# GSM.net
KiCad netlist of a schematic drawn in Altium Designer
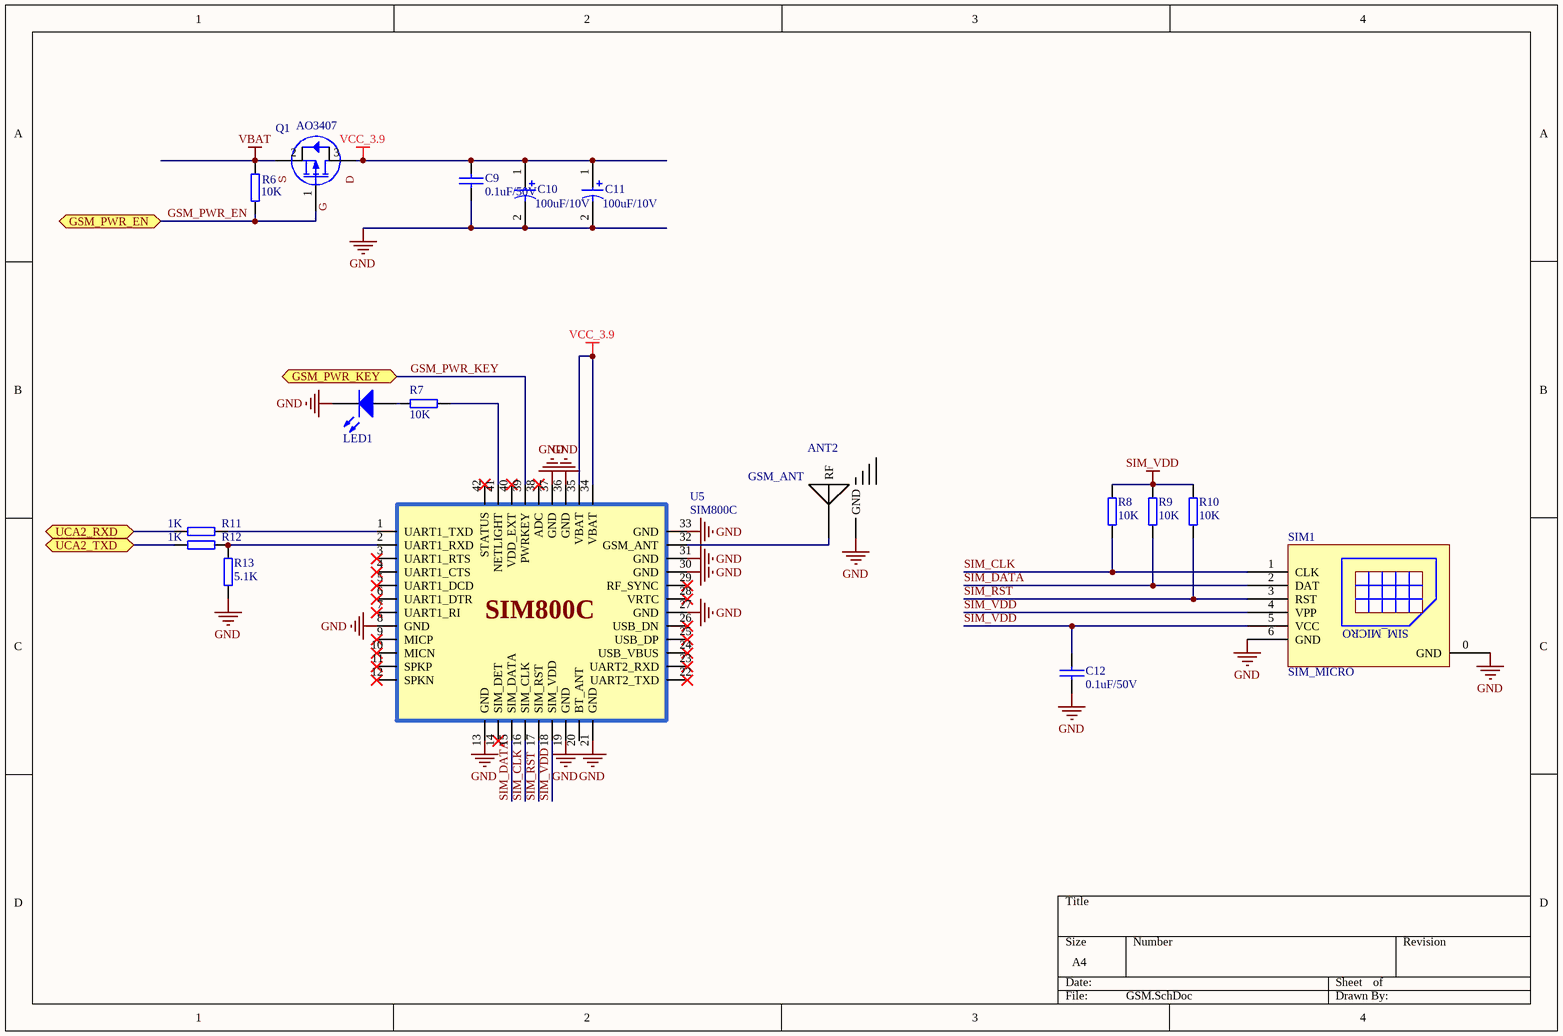
[diagram p0: GSM.SchDoc]

(export (version "E")
  (design (tool "Eeschema 10.0.6"))
  (components
    (comp (ref "ANT2")
      (value "GSM_ANT")
      (footprint "IPEX")
      (description "passive_antenna")
      (libsource (lib "GBOX_V2") (part "GSM_ANT_1"))
    )
    (comp (ref "C9")
      (value "0.1uF/50V")
      (footprint "0603C")
      (description "Capacitor")
      (libsource (lib "0603C") (part "CAP"))
    )
    (comp (ref "C10") (value "100uF/10V") (footprint "CAPTANC") (libsource (lib "*") (part "CAP2")))
    (comp (ref "C11") (value "100uF/10V") (footprint "CAPTANC") (libsource (lib "*") (part "CAP2")))
    (comp (ref "C12") (value "0.1uF/50V") (footprint "0603C") (libsource (lib "Schlib") (part "0603C")))
    (comp (ref "LED1")
      (value "YLED")
      (footprint "LED-0603")
      (description "BLUE LED")
      (fields (field (name "PUBLISHER") "Altium Limited"))
      (libsource (lib "Schlib") (part "LED3"))
    )
    (comp (ref "Q1")
      (value "AO3407")
      (footprint "SOT23")
      (description "P-Channel MOSFET")
      (fields (field (name "PUBLISHER") "Altium Limited"))
      (libsource (lib "SCT1212V100") (part "AO3401"))
    )
    (comp (ref "R6") (value "10K") (footprint "0603R") (libsource (lib "dtu02") (part "RES2A")))
    (comp (ref "R7") (value "10K") (footprint "0603R") (libsource (lib "dtu02") (part "RES2A")))
    (comp (ref "R8") (value "10K") (footprint "0603R") (libsource (lib "dtu02") (part "RES2A")))
    (comp (ref "R9") (value "10K") (footprint "0603R") (libsource (lib "dtu02") (part "RES2A")))
    (comp (ref "R10") (value "10K") (footprint "0603R") (libsource (lib "dtu02") (part "RES2A")))
    (comp (ref "R11") (value "1K") (footprint "0603R") (libsource (lib "dtu02") (part "RES2A")))
    (comp (ref "R12") (value "1K") (footprint "0603R") (libsource (lib "dtu02") (part "RES2A")))
    (comp (ref "R13") (value "5.1K") (footprint "0603R") (libsource (lib "dtu02") (part "RES2A")))
    (comp (ref "SIM1")
      (value "SIM_MICRO")
      (footprint "SIM_MICRO")
      (libsource (lib "GBOX_V2") (part "SIM_MICRO"))
    )
    (comp (ref "U5") (value "SIM800C") (footprint "SIM800C") (libsource (lib "GBOX_V2") (part "SIM800C")))
  )
  (nets
    (net (code "1") (name "/GSM_PWR_EN") (class "Default")
      (node (ref "Q1") (pin "1") (pinfunction "G_1") (pintype "passive"))
      (node (ref "R6") (pin "2") (pintype "passive"))
    )
    (net (code "2") (name "/GSM_PWR_KEY") (class "Default")
      (node (ref "U5") (pin "39") (pinfunction "PWRKEY_39") (pintype "passive"))
    )
    (net (code "3") (name "/SIM_CLK") (class "Default")
      (node (ref "R8") (pin "2") (pintype "passive"))
      (node (ref "SIM1") (pin "1") (pinfunction "CLK_1") (pintype "passive"))
      (node (ref "U5") (pin "16") (pinfunction "SIM_CLK_16") (pintype "passive"))
    )
    (net (code "4") (name "/SIM_DATA") (class "Default")
      (node (ref "R9") (pin "2") (pintype "passive"))
      (node (ref "SIM1") (pin "2") (pinfunction "DAT_2") (pintype "passive"))
      (node (ref "U5") (pin "15") (pinfunction "SIM_DATA_15") (pintype "passive"))
    )
    (net (code "5") (name "/SIM_RST") (class "Default")
      (node (ref "R10") (pin "2") (pintype "passive"))
      (node (ref "SIM1") (pin "3") (pinfunction "RST_3") (pintype "passive"))
      (node (ref "U5") (pin "17") (pinfunction "SIM_RST_17") (pintype "passive"))
    )
    (net (code "6") (name "/UCA2_RXD") (class "Default") (node (ref "R11") (pin "1") (pintype "passive")))
    (net (code "7") (name "/UCA2_TXD") (class "Default") (node (ref "R12") (pin "1") (pintype "passive")))
    (net (code "8") (name "GND") (class "Default")
      (node (ref "ANT2") (pin "1") (pinfunction "GND_1") (pintype "passive"))
      (node (ref "C10") (pin "2") (pinfunction "2_2") (pintype "passive"))
      (node (ref "C11") (pin "2") (pinfunction "2_2") (pintype "passive"))
      (node (ref "C12") (pin "2") (pintype "passive"))
      (node (ref "C9") (pin "2") (pinfunction "2_2") (pintype "passive"))
      (node (ref "LED1") (pin "2") (pinfunction "K_2") (pintype "passive"))
      (node (ref "R13") (pin "2") (pintype "passive"))
      (node (ref "SIM1") (pin "0") (pinfunction "GND_0") (pintype "passive"))
      (node (ref "SIM1") (pin "6") (pinfunction "GND_6") (pintype "passive"))
      (node (ref "U5") (pin "13") (pinfunction "GND_13") (pintype "passive"))
      (node (ref "U5") (pin "19") (pinfunction "GND_19") (pintype "passive"))
      (node (ref "U5") (pin "21") (pinfunction "GND_21") (pintype "passive"))
      (node (ref "U5") (pin "27") (pinfunction "GND_27") (pintype "passive"))
      (node (ref "U5") (pin "30") (pinfunction "GND_30") (pintype "passive"))
      (node (ref "U5") (pin "31") (pinfunction "GND_31") (pintype "passive"))
      (node (ref "U5") (pin "33") (pinfunction "GND_33") (pintype "passive"))
      (node (ref "U5") (pin "36") (pinfunction "GND_36") (pintype "passive"))
      (node (ref "U5") (pin "37") (pinfunction "GND_37") (pintype "passive"))
      (node (ref "U5") (pin "8") (pinfunction "GND_8") (pintype "passive"))
    )
    (net (code "9") (name "Net-(ANT2-RF)") (class "Default")
      (node (ref "ANT2") (pin "2") (pinfunction "RF_2") (pintype "passive"))
      (node (ref "U5") (pin "32") (pinfunction "GSM_ANT_32") (pintype "passive"))
    )
    (net (code "10") (name "Net-(LED1-A)") (class "Default")
      (node (ref "LED1") (pin "1") (pinfunction "A_1") (pintype "passive"))
      (node (ref "R7") (pin "2") (pintype "passive"))
    )
    (net (code "11") (name "Net-(U5-NETLIGHT)") (class "Default")
      (node (ref "R7") (pin "1") (pintype "passive"))
      (node (ref "U5") (pin "41") (pinfunction "NETLIGHT_41") (pintype "passive"))
    )
    (net (code "12") (name "Net-(U5-UART1_RXD)") (class "Default")
      (node (ref "R12") (pin "2") (pintype "passive"))
      (node (ref "R13") (pin "1") (pintype "passive"))
      (node (ref "U5") (pin "2") (pinfunction "UART1_RXD_2") (pintype "passive"))
    )
    (net (code "13") (name "Net-(U5-UART1_TXD)") (class "Default")
      (node (ref "R11") (pin "2") (pintype "passive"))
      (node (ref "U5") (pin "1") (pinfunction "UART1_TXD_1") (pintype "passive"))
    )
    (net (code "14") (name "SIM_VDD") (class "Default")
      (node (ref "C12") (pin "1") (pintype "passive"))
      (node (ref "R10") (pin "1") (pintype "passive"))
      (node (ref "R8") (pin "1") (pintype "passive"))
      (node (ref "R9") (pin "1") (pintype "passive"))
      (node (ref "SIM1") (pin "4") (pinfunction "VPP_4") (pintype "passive"))
      (node (ref "SIM1") (pin "5") (pinfunction "VCC_5") (pintype "passive"))
      (node (ref "U5") (pin "18") (pinfunction "SIM_VDD_18") (pintype "passive"))
    )
    (net (code "15") (name "VBAT") (class "Default")
      (node (ref "Q1") (pin "2") (pinfunction "S_2") (pintype "passive"))
      (node (ref "R6") (pin "1") (pintype "passive"))
    )
    (net (code "16") (name "VCC_3.9") (class "Default")
      (node (ref "C10") (pin "1") (pinfunction "1_1") (pintype "passive"))
      (node (ref "C11") (pin "1") (pinfunction "1_1") (pintype "passive"))
      (node (ref "C9") (pin "1") (pinfunction "1_1") (pintype "passive"))
      (node (ref "Q1") (pin "3") (pinfunction "D_3") (pintype "passive"))
      (node (ref "U5") (pin "34") (pinfunction "VBAT_34") (pintype "passive"))
      (node (ref "U5") (pin "35") (pinfunction "VBAT_35") (pintype "passive"))
    )
    (net (code "17") (name "unconnected-(U5-ADC-Pad38)") (class "Default")
      (node (ref "U5") (pin "38") (pinfunction "ADC_38") (pintype "passive+no_connect"))
    )
    (net (code "18") (name "unconnected-(U5-BT_ANT-Pad20)") (class "Default")
      (node (ref "U5") (pin "20") (pinfunction "BT_ANT_20") (pintype "passive"))
    )
    (net (code "19") (name "unconnected-(U5-MICN-Pad10)") (class "Default")
      (node (ref "U5") (pin "10") (pinfunction "MICN_10") (pintype "passive+no_connect"))
    )
    (net (code "20") (name "unconnected-(U5-MICP-Pad9)") (class "Default")
      (node (ref "U5") (pin "9") (pinfunction "MICP_9") (pintype "passive+no_connect"))
    )
    (net (code "21") (name "unconnected-(U5-RF_SYNC-Pad29)") (class "Default")
      (node (ref "U5") (pin "29") (pinfunction "RF_SYNC_29") (pintype "passive+no_connect"))
    )
    (net (code "22") (name "unconnected-(U5-SIM_DET-Pad14)") (class "Default")
      (node (ref "U5") (pin "14") (pinfunction "SIM_DET_14") (pintype "passive+no_connect"))
    )
    (net (code "23") (name "unconnected-(U5-SPKN-Pad12)") (class "Default")
      (node (ref "U5") (pin "12") (pinfunction "SPKN_12") (pintype "passive+no_connect"))
    )
    (net (code "24") (name "unconnected-(U5-SPKP-Pad11)") (class "Default")
      (node (ref "U5") (pin "11") (pinfunction "SPKP_11") (pintype "passive+no_connect"))
    )
    (net (code "25") (name "unconnected-(U5-STATUS-Pad42)") (class "Default")
      (node (ref "U5") (pin "42") (pinfunction "STATUS_42") (pintype "passive+no_connect"))
    )
    (net (code "26") (name "unconnected-(U5-UART1_CTS-Pad4)") (class "Default")
      (node (ref "U5") (pin "4") (pinfunction "UART1_CTS_4") (pintype "passive+no_connect"))
    )
    (net (code "27") (name "unconnected-(U5-UART1_DCD-Pad5)") (class "Default")
      (node (ref "U5") (pin "5") (pinfunction "UART1_DCD_5") (pintype "passive+no_connect"))
    )
    (net (code "28") (name "unconnected-(U5-UART1_DTR-Pad6)") (class "Default")
      (node (ref "U5") (pin "6") (pinfunction "UART1_DTR_6") (pintype "passive+no_connect"))
    )
    (net (code "29") (name "unconnected-(U5-UART1_RI-Pad7)") (class "Default")
      (node (ref "U5") (pin "7") (pinfunction "UART1_RI_7") (pintype "passive+no_connect"))
    )
    (net (code "30") (name "unconnected-(U5-UART1_RTS-Pad3)") (class "Default")
      (node (ref "U5") (pin "3") (pinfunction "UART1_RTS_3") (pintype "passive+no_connect"))
    )
    (net (code "31") (name "unconnected-(U5-UART2_RXD-Pad23)") (class "Default")
      (node (ref "U5") (pin "23") (pinfunction "UART2_RXD_23") (pintype "passive+no_connect"))
    )
    (net (code "32") (name "unconnected-(U5-UART2_TXD-Pad22)") (class "Default")
      (node (ref "U5") (pin "22") (pinfunction "UART2_TXD_22") (pintype "passive+no_connect"))
    )
    (net (code "33") (name "unconnected-(U5-USB_DN-Pad26)") (class "Default")
      (node (ref "U5") (pin "26") (pinfunction "USB_DN_26") (pintype "passive+no_connect"))
    )
    (net (code "34") (name "unconnected-(U5-USB_DP-Pad25)") (class "Default")
      (node (ref "U5") (pin "25") (pinfunction "USB_DP_25") (pintype "passive+no_connect"))
    )
    (net (code "35") (name "unconnected-(U5-USB_VBUS-Pad24)") (class "Default")
      (node (ref "U5") (pin "24") (pinfunction "USB_VBUS_24") (pintype "passive+no_connect"))
    )
    (net (code "36") (name "unconnected-(U5-VDD_EXT-Pad40)") (class "Default")
      (node (ref "U5") (pin "40") (pinfunction "VDD_EXT_40") (pintype "passive+no_connect"))
    )
    (net (code "37") (name "unconnected-(U5-VRTC-Pad28)") (class "Default")
      (node (ref "U5") (pin "28") (pinfunction "VRTC_28") (pintype "passive+no_connect"))
    )
  )
)
